# Esquema_el_tric.net
KiCad netlist of a schematic drawn in EAGLE
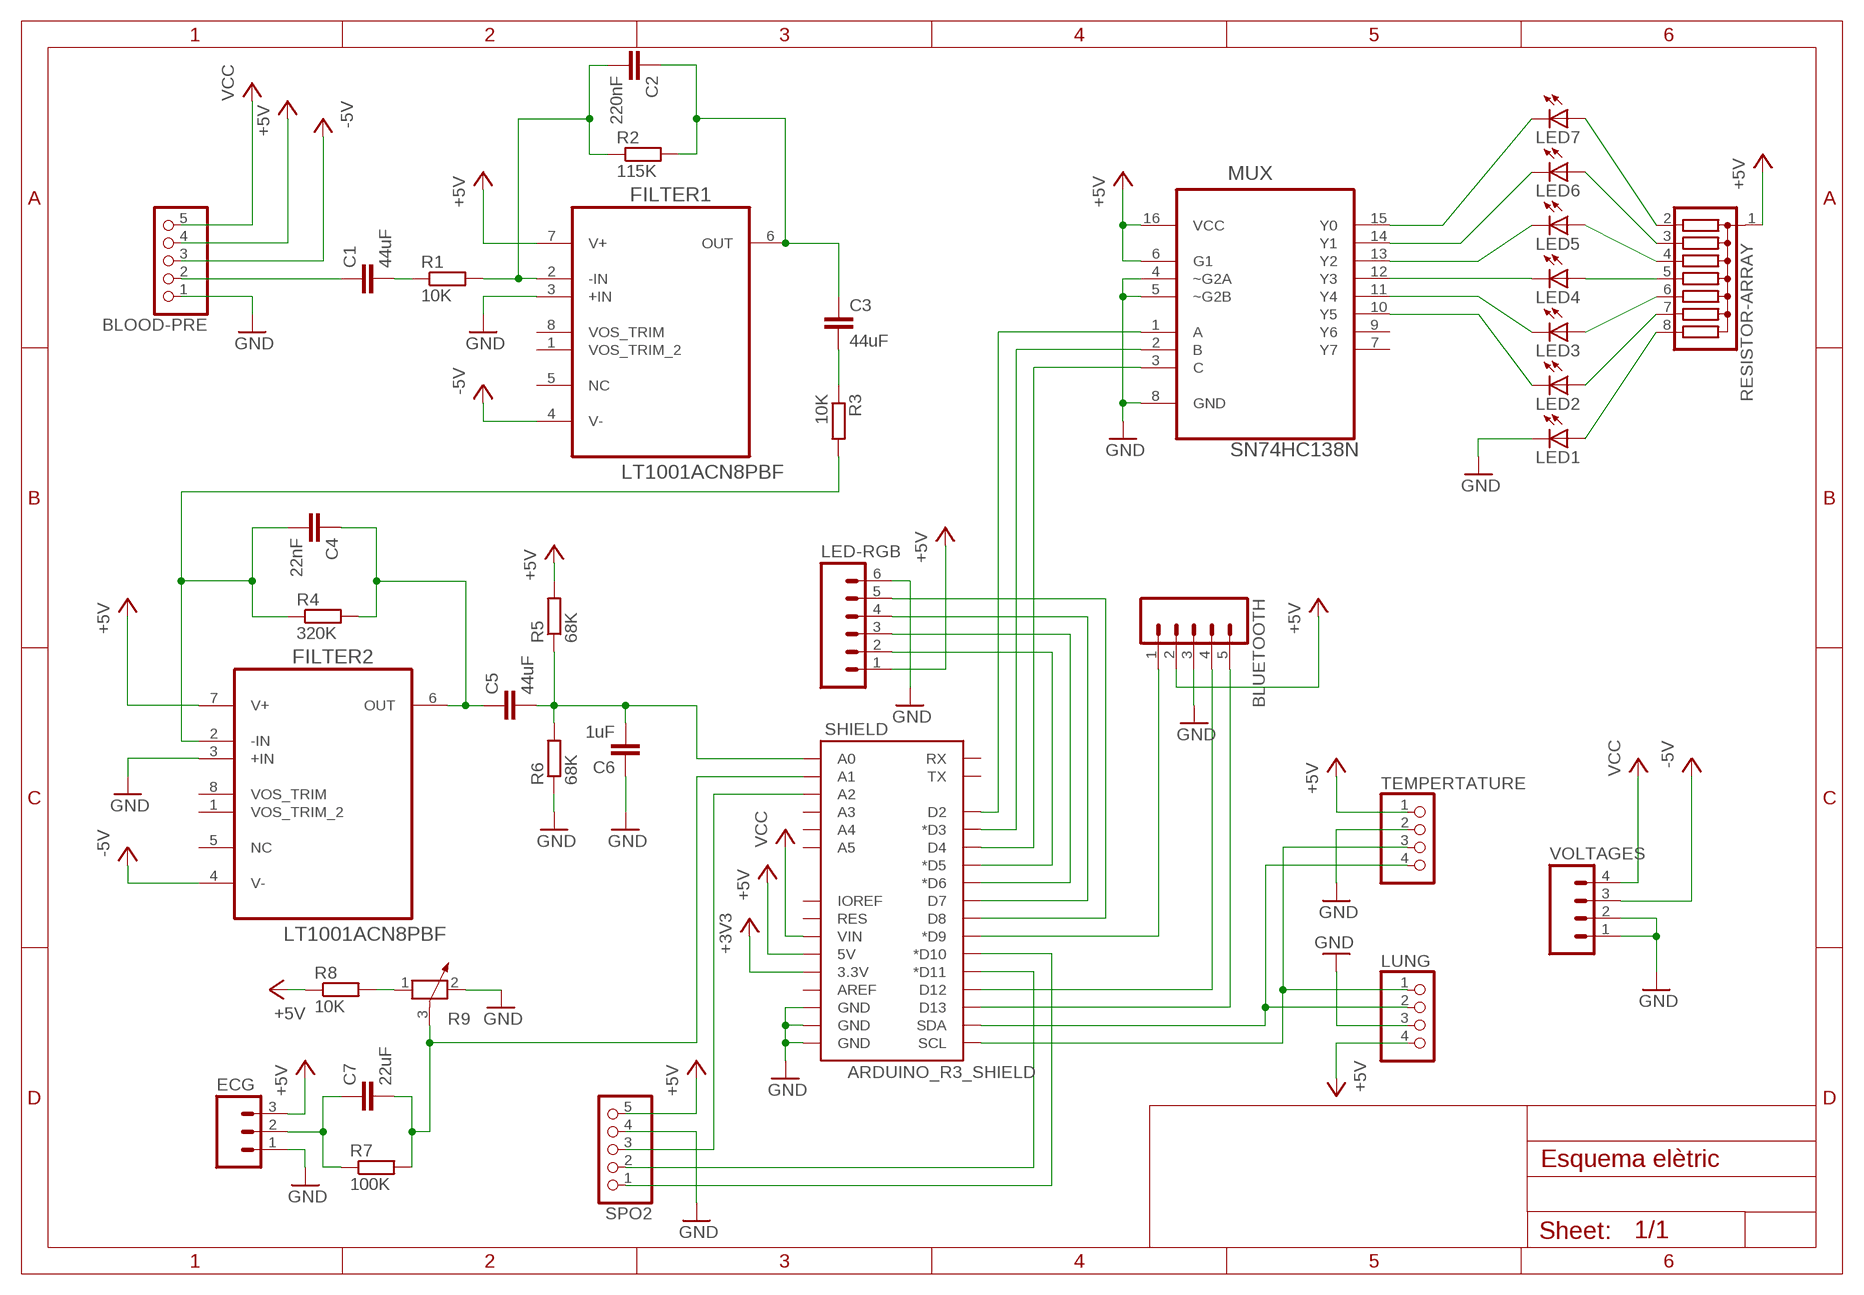
[diagram p0: schematic, sheet 1]

(export (version "E")
  (design (tool "Eeschema 10.0.6"))
  (components
    (comp (ref "BLOOD-PRE")
      (value "PINHD-1X5")
      (footprint "eagle-import:1X05")
      (libsource (lib "eagle-import") (part "PINHD-1X5"))
    )
    (comp (ref "BLUETOOTH")
      (value "M05PTH")
      (footprint "eagle-import:1X05")
      (libsource (lib "eagle-import") (part "M05PTH"))
    )
    (comp (ref "C1")
      (value "44uF")
      (footprint "eagle-import:C050-050X075")
      (libsource (lib "eagle-import") (part "C-EU050-050X075"))
    )
    (comp (ref "C2")
      (value "220nF")
      (footprint "eagle-import:C050-024X044")
      (libsource (lib "eagle-import") (part "C-EU050-024X044"))
    )
    (comp (ref "C3")
      (value "44uF")
      (footprint "eagle-import:C050-050X075")
      (libsource (lib "eagle-import") (part "C-EU050-050X075"))
    )
    (comp (ref "C4")
      (value "22nF")
      (footprint "eagle-import:C050-024X044")
      (libsource (lib "eagle-import") (part "C-EU050-024X044"))
    )
    (comp (ref "C5")
      (value "44uF")
      (footprint "eagle-import:C050-050X075")
      (libsource (lib "eagle-import") (part "C-EU050-050X075"))
    )
    (comp (ref "C6")
      (value "1uF")
      (footprint "eagle-import:C050-050X075")
      (libsource (lib "eagle-import") (part "C-EU050-050X075"))
    )
    (comp (ref "C7")
      (value "22uF")
      (footprint "eagle-import:C050-050X075")
      (libsource (lib "eagle-import") (part "C-EU050-050X075"))
    )
    (comp (ref "ECG")
      (value "M03PTH")
      (footprint "eagle-import:1X03")
      (libsource (lib "eagle-import") (part "M03PTH"))
    )
    (comp (ref "FILTER1")
      (value "LT1001ACN8PBF")
      (footprint "eagle-import:DIP254P762X393-8")
      (fields (field (name "MPN") "LT1001ACN8#PBF"))
      (libsource (lib "eagle-import") (part "LT1001ACN8PBF"))
    )
    (comp (ref "FILTER2")
      (value "LT1001ACN8PBF")
      (footprint "eagle-import:DIP254P762X393-8")
      (fields (field (name "MPN") "LT1001ACN8#PBF"))
      (libsource (lib "eagle-import") (part "LT1001ACN8PBF"))
    )
    (comp (ref "LED-RGB")
      (value "M06SILK_FEMALE_PTH")
      (footprint "eagle-import:1X06")
      (libsource (lib "eagle-import") (part "M06SILK_FEMALE_PTH"))
    )
    (comp (ref "LED1")
      (value "LED5MM")
      (footprint "eagle-import:LED5MM")
      (libsource (lib "eagle-import") (part "LED5MM"))
    )
    (comp (ref "LED2")
      (value "LED5MM")
      (footprint "eagle-import:LED5MM")
      (libsource (lib "eagle-import") (part "LED5MM"))
    )
    (comp (ref "LED3")
      (value "LED5MM")
      (footprint "eagle-import:LED5MM")
      (libsource (lib "eagle-import") (part "LED5MM"))
    )
    (comp (ref "LED4")
      (value "LED5MM")
      (footprint "eagle-import:LED5MM")
      (libsource (lib "eagle-import") (part "LED5MM"))
    )
    (comp (ref "LED5")
      (value "LED5MM")
      (footprint "eagle-import:LED5MM")
      (libsource (lib "eagle-import") (part "LED5MM"))
    )
    (comp (ref "LED6")
      (value "LED5MM")
      (footprint "eagle-import:LED5MM")
      (libsource (lib "eagle-import") (part "LED5MM"))
    )
    (comp (ref "LED7")
      (value "LED5MM")
      (footprint "eagle-import:LED5MM")
      (libsource (lib "eagle-import") (part "LED5MM"))
    )
    (comp (ref "LUNG")
      (value "PINHD-1X4")
      (footprint "eagle-import:1X04")
      (libsource (lib "eagle-import") (part "PINHD-1X4"))
    )
    (comp (ref "MUX")
      (value "SN74HC138N")
      (footprint "eagle-import:DIP254P762X508-16")
      (libsource (lib "eagle-import") (part "SN74HC138N"))
    )
    (comp (ref "R1")
      (value "10K")
      (footprint "eagle-import:0204_7")
      (libsource (lib "eagle-import") (part "R0204/7"))
    )
    (comp (ref "R2")
      (value "115K")
      (footprint "eagle-import:0204_7")
      (libsource (lib "eagle-import") (part "R0204/7"))
    )
    (comp (ref "R3")
      (value "10K")
      (footprint "eagle-import:0204_7")
      (libsource (lib "eagle-import") (part "R0204/7"))
    )
    (comp (ref "R4")
      (value "320K")
      (footprint "eagle-import:0204_7")
      (libsource (lib "eagle-import") (part "R0204/7"))
    )
    (comp (ref "R5")
      (value "68K")
      (footprint "eagle-import:0204_7")
      (libsource (lib "eagle-import") (part "R0204/7"))
    )
    (comp (ref "R6")
      (value "68K")
      (footprint "eagle-import:0204_7")
      (libsource (lib "eagle-import") (part "R0204/7"))
    )
    (comp (ref "R7")
      (value "100K")
      (footprint "eagle-import:0204_7")
      (libsource (lib "eagle-import") (part "R0204/7"))
    )
    (comp (ref "R8")
      (value "10K")
      (footprint "eagle-import:0204_7")
      (libsource (lib "eagle-import") (part "R0204/7"))
    )
    (comp (ref "R9")
      (value "POTENTIOMETER_PT-10")
      (footprint "eagle-import:PT-10")
      (libsource (lib "eagle-import") (part "POTENTIOMETER_PT-10"))
    )
    (comp (ref "RESISTOR-ARRAY")
      (value "G07R")
      (footprint "eagle-import:SIL8")
      (libsource (lib "eagle-import") (part "G07R"))
    )
    (comp (ref "SHIELD")
      (value "ARDUINO_R3_SHIELD")
      (footprint "eagle-import:UNO_R3_SHIELD")
      (libsource (lib "eagle-import") (part "ARDUINO_R3_SHIELD"))
    )
    (comp (ref "SPO2")
      (value "PINHD-1X5")
      (footprint "eagle-import:1X05")
      (libsource (lib "eagle-import") (part "PINHD-1X5"))
    )
    (comp (ref "TEMPERTATURE")
      (value "PINHD-1X4")
      (footprint "eagle-import:1X04")
      (libsource (lib "eagle-import") (part "PINHD-1X4"))
    )
    (comp (ref "VOLTAGES")
      (value "M04JST")
      (footprint "eagle-import:1X04-1.5MM_JST")
      (libsource (lib "eagle-import") (part "M04JST"))
    )
  )
  (nets
    (net (code "1") (name "+3V3") (class "Default")
      (node (ref "SHIELD") (pin "3.3V") (pinfunction "3.3V_3.3V") (pintype "bidirectional"))
    )
    (net (code "2") (name "+5V") (class "Default")
      (node (ref "BLOOD-PRE") (pin "4") (pinfunction "4_4") (pintype "passive"))
      (node (ref "BLUETOOTH") (pin "2") (pinfunction "2_2") (pintype "passive"))
      (node (ref "ECG") (pin "3") (pinfunction "3_3") (pintype "passive"))
      (node (ref "FILTER1") (pin "7") (pinfunction "V+_7") (pintype "power_in"))
      (node (ref "FILTER2") (pin "7") (pinfunction "V+_7") (pintype "power_in"))
      (node (ref "LED-RGB") (pin "1") (pinfunction "1_1") (pintype "passive"))
      (node (ref "LUNG") (pin "4") (pinfunction "4_4") (pintype "passive"))
      (node (ref "MUX") (pin "16") (pinfunction "VCC_16") (pintype "power_in"))
      (node (ref "MUX") (pin "6") (pinfunction "G1_6") (pintype "input"))
      (node (ref "R5") (pin "2") (pinfunction "2_2") (pintype "passive"))
      (node (ref "R8") (pin "1") (pinfunction "1_1") (pintype "passive"))
      (node (ref "RESISTOR-ARRAY") (pin "1") (pinfunction "1_1") (pintype "passive"))
      (node (ref "SHIELD") (pin "5V") (pinfunction "5V_5V") (pintype "bidirectional"))
      (node (ref "SPO2") (pin "5") (pinfunction "5_5") (pintype "passive"))
      (node (ref "TEMPERTATURE") (pin "1") (pinfunction "1_1") (pintype "passive"))
    )
    (net (code "3") (name "-5V") (class "Default")
      (node (ref "BLOOD-PRE") (pin "3") (pinfunction "3_3") (pintype "passive"))
      (node (ref "FILTER1") (pin "4") (pinfunction "V-_4") (pintype "power_in"))
      (node (ref "FILTER2") (pin "4") (pinfunction "V-_4") (pintype "power_in"))
      (node (ref "VOLTAGES") (pin "3") (pinfunction "3_3") (pintype "passive"))
    )
    (net (code "4") (name "GND") (class "Default")
      (node (ref "BLOOD-PRE") (pin "1") (pinfunction "1_1") (pintype "passive"))
      (node (ref "BLUETOOTH") (pin "3") (pinfunction "3_3") (pintype "passive"))
      (node (ref "C6") (pin "1") (pinfunction "1_1") (pintype "passive"))
      (node (ref "ECG") (pin "1") (pinfunction "1_1") (pintype "passive"))
      (node (ref "FILTER1") (pin "3") (pinfunction "+IN_3") (pintype "input"))
      (node (ref "FILTER2") (pin "3") (pinfunction "+IN_3") (pintype "input"))
      (node (ref "LED-RGB") (pin "6") (pinfunction "6_6") (pintype "passive"))
      (node (ref "LED1") (pin "K") (pinfunction "C_K") (pintype "passive"))
      (node (ref "LUNG") (pin "3") (pinfunction "3_3") (pintype "passive"))
      (node (ref "MUX") (pin "4") (pinfunction "~{G2A}_4") (pintype "input"))
      (node (ref "MUX") (pin "5") (pinfunction "~{G2B}_5") (pintype "input"))
      (node (ref "MUX") (pin "8") (pinfunction "GND_8") (pintype "passive"))
      (node (ref "R6") (pin "1") (pinfunction "1_1") (pintype "passive"))
      (node (ref "R9") (pin "2") (pinfunction "2_2") (pintype "passive"))
      (node (ref "SHIELD") (pin "GND@0") (pinfunction "GND_GND@0") (pintype "bidirectional"))
      (node (ref "SHIELD") (pin "GND@1") (pinfunction "GND_GND@1") (pintype "bidirectional"))
      (node (ref "SHIELD") (pin "GND@2") (pinfunction "GND_GND@2") (pintype "bidirectional"))
      (node (ref "SPO2") (pin "4") (pinfunction "4_4") (pintype "passive"))
      (node (ref "TEMPERTATURE") (pin "2") (pinfunction "2_2") (pintype "passive"))
      (node (ref "VOLTAGES") (pin "1") (pinfunction "1_1") (pintype "passive"))
      (node (ref "VOLTAGES") (pin "2") (pinfunction "2_2") (pintype "passive"))
    )
    (net (code "5") (name "Net-(BLOOD-PRE-Pad2)") (class "Default")
      (node (ref "BLOOD-PRE") (pin "2") (pinfunction "2_2") (pintype "passive"))
      (node (ref "C1") (pin "1") (pinfunction "1_1") (pintype "passive"))
    )
    (net (code "6") (name "Net-(BLUETOOTH-Pad4)") (class "Default")
      (node (ref "BLUETOOTH") (pin "4") (pinfunction "4_4") (pintype "passive"))
      (node (ref "SHIELD") (pin "D12") (pinfunction "D12_D12") (pintype "bidirectional"))
    )
    (net (code "7") (name "Net-(BLUETOOTH-Pad5)") (class "Default")
      (node (ref "BLUETOOTH") (pin "5") (pinfunction "5_5") (pintype "passive"))
      (node (ref "SHIELD") (pin "D13") (pinfunction "D13_D13") (pintype "bidirectional"))
    )
    (net (code "8") (name "Net-(C1-Pad2)") (class "Default")
      (node (ref "C1") (pin "2") (pinfunction "2_2") (pintype "passive"))
      (node (ref "R1") (pin "1") (pinfunction "1_1") (pintype "passive"))
    )
    (net (code "9") (name "Net-(C3-Pad2)") (class "Default")
      (node (ref "C3") (pin "2") (pinfunction "2_2") (pintype "passive"))
      (node (ref "R3") (pin "1") (pinfunction "1_1") (pintype "passive"))
    )
    (net (code "10") (name "Net-(C5-Pad2)") (class "Default")
      (node (ref "C5") (pin "2") (pinfunction "2_2") (pintype "passive"))
      (node (ref "C6") (pin "2") (pinfunction "2_2") (pintype "passive"))
      (node (ref "R5") (pin "1") (pinfunction "1_1") (pintype "passive"))
      (node (ref "R6") (pin "2") (pinfunction "2_2") (pintype "passive"))
      (node (ref "SHIELD") (pin "A0") (pinfunction "A0_A0") (pintype "bidirectional"))
    )
    (net (code "11") (name "Net-(C7-Pad1)") (class "Default")
      (node (ref "C7") (pin "1") (pinfunction "1_1") (pintype "passive"))
      (node (ref "ECG") (pin "2") (pinfunction "2_2") (pintype "passive"))
      (node (ref "R7") (pin "1") (pinfunction "1_1") (pintype "passive"))
    )
    (net (code "12") (name "Net-(C7-Pad2)") (class "Default")
      (node (ref "C7") (pin "2") (pinfunction "2_2") (pintype "passive"))
      (node (ref "R7") (pin "2") (pinfunction "2_2") (pintype "passive"))
      (node (ref "R9") (pin "3") (pinfunction "3_3") (pintype "passive"))
      (node (ref "SHIELD") (pin "A1") (pinfunction "A1_A1") (pintype "bidirectional"))
    )
    (net (code "13") (name "Net-(FILTER1--IN)") (class "Default")
      (node (ref "C2") (pin "2") (pinfunction "2_2") (pintype "passive"))
      (node (ref "FILTER1") (pin "2") (pinfunction "-IN_2") (pintype "input"))
      (node (ref "R1") (pin "2") (pinfunction "2_2") (pintype "passive"))
      (node (ref "R2") (pin "1") (pinfunction "1_1") (pintype "passive"))
    )
    (net (code "14") (name "Net-(FILTER1-OUT)") (class "Default")
      (node (ref "C2") (pin "1") (pinfunction "1_1") (pintype "passive"))
      (node (ref "C3") (pin "1") (pinfunction "1_1") (pintype "passive"))
      (node (ref "FILTER1") (pin "6") (pinfunction "OUT_6") (pintype "output"))
      (node (ref "R2") (pin "2") (pinfunction "2_2") (pintype "passive"))
    )
    (net (code "15") (name "Net-(FILTER2--IN)") (class "Default")
      (node (ref "C4") (pin "2") (pinfunction "2_2") (pintype "passive"))
      (node (ref "FILTER2") (pin "2") (pinfunction "-IN_2") (pintype "input"))
      (node (ref "R3") (pin "2") (pinfunction "2_2") (pintype "passive"))
      (node (ref "R4") (pin "1") (pinfunction "1_1") (pintype "passive"))
    )
    (net (code "16") (name "Net-(FILTER2-OUT)") (class "Default")
      (node (ref "C4") (pin "1") (pinfunction "1_1") (pintype "passive"))
      (node (ref "C5") (pin "1") (pinfunction "1_1") (pintype "passive"))
      (node (ref "FILTER2") (pin "6") (pinfunction "OUT_6") (pintype "output"))
      (node (ref "R4") (pin "2") (pinfunction "2_2") (pintype "passive"))
    )
    (net (code "17") (name "Net-(LED-RGB-Pad4)") (class "Default")
      (node (ref "LED-RGB") (pin "4") (pinfunction "4_4") (pintype "passive"))
      (node (ref "SHIELD") (pin "D7") (pinfunction "D7_D7") (pintype "bidirectional"))
    )
    (net (code "18") (name "Net-(LED-RGB-Pad5)") (class "Default")
      (node (ref "LED-RGB") (pin "5") (pinfunction "5_5") (pintype "passive"))
      (node (ref "SHIELD") (pin "D8") (pinfunction "D8_D8") (pintype "bidirectional"))
    )
    (net (code "19") (name "Net-(LED1-PadA)") (class "Default")
      (node (ref "LED1") (pin "A") (pinfunction "A_A") (pintype "passive"))
      (node (ref "RESISTOR-ARRAY") (pin "8") (pinfunction "8_8") (pintype "passive"))
    )
    (net (code "20") (name "Net-(LED2-C)") (class "Default")
      (node (ref "LED2") (pin "K") (pinfunction "C_K") (pintype "passive"))
      (node (ref "MUX") (pin "10") (pinfunction "Y5_10") (pintype "output"))
    )
    (net (code "21") (name "Net-(LED2-PadA)") (class "Default")
      (node (ref "LED2") (pin "A") (pinfunction "A_A") (pintype "passive"))
      (node (ref "RESISTOR-ARRAY") (pin "7") (pinfunction "7_7") (pintype "passive"))
    )
    (net (code "22") (name "Net-(LED3-C)") (class "Default")
      (node (ref "LED3") (pin "K") (pinfunction "C_K") (pintype "passive"))
      (node (ref "MUX") (pin "11") (pinfunction "Y4_11") (pintype "output"))
    )
    (net (code "23") (name "Net-(LED3-PadA)") (class "Default")
      (node (ref "LED3") (pin "A") (pinfunction "A_A") (pintype "passive"))
      (node (ref "RESISTOR-ARRAY") (pin "6") (pinfunction "6_6") (pintype "passive"))
    )
    (net (code "24") (name "Net-(LED4-C)") (class "Default")
      (node (ref "LED4") (pin "K") (pinfunction "C_K") (pintype "passive"))
      (node (ref "MUX") (pin "12") (pinfunction "Y3_12") (pintype "output"))
    )
    (net (code "25") (name "Net-(LED4-PadA)") (class "Default")
      (node (ref "LED4") (pin "A") (pinfunction "A_A") (pintype "passive"))
      (node (ref "RESISTOR-ARRAY") (pin "5") (pinfunction "5_5") (pintype "passive"))
    )
    (net (code "26") (name "Net-(LED5-C)") (class "Default")
      (node (ref "LED5") (pin "K") (pinfunction "C_K") (pintype "passive"))
      (node (ref "MUX") (pin "13") (pinfunction "Y2_13") (pintype "output"))
    )
    (net (code "27") (name "Net-(LED5-PadA)") (class "Default")
      (node (ref "LED5") (pin "A") (pinfunction "A_A") (pintype "passive"))
      (node (ref "RESISTOR-ARRAY") (pin "4") (pinfunction "4_4") (pintype "passive"))
    )
    (net (code "28") (name "Net-(LED6-C)") (class "Default")
      (node (ref "LED6") (pin "K") (pinfunction "C_K") (pintype "passive"))
      (node (ref "MUX") (pin "14") (pinfunction "Y1_14") (pintype "output"))
    )
    (net (code "29") (name "Net-(LED6-PadA)") (class "Default")
      (node (ref "LED6") (pin "A") (pinfunction "A_A") (pintype "passive"))
      (node (ref "RESISTOR-ARRAY") (pin "3") (pinfunction "3_3") (pintype "passive"))
    )
    (net (code "30") (name "Net-(LED7-C)") (class "Default")
      (node (ref "LED7") (pin "K") (pinfunction "C_K") (pintype "passive"))
      (node (ref "MUX") (pin "15") (pinfunction "Y0_15") (pintype "output"))
    )
    (net (code "31") (name "Net-(LED7-PadA)") (class "Default")
      (node (ref "LED7") (pin "A") (pinfunction "A_A") (pintype "passive"))
      (node (ref "RESISTOR-ARRAY") (pin "2") (pinfunction "2_2") (pintype "passive"))
    )
    (net (code "32") (name "Net-(LUNG-Pad1)") (class "Default")
      (node (ref "LUNG") (pin "1") (pinfunction "1_1") (pintype "passive"))
      (node (ref "SHIELD") (pin "SCL") (pinfunction "SCL_SCL") (pintype "bidirectional"))
      (node (ref "TEMPERTATURE") (pin "3") (pinfunction "3_3") (pintype "passive"))
    )
    (net (code "33") (name "Net-(LUNG-Pad2)") (class "Default")
      (node (ref "LUNG") (pin "2") (pinfunction "2_2") (pintype "passive"))
      (node (ref "SHIELD") (pin "SDA") (pinfunction "SDA_SDA") (pintype "bidirectional"))
      (node (ref "TEMPERTATURE") (pin "4") (pinfunction "4_4") (pintype "passive"))
    )
    (net (code "34") (name "Net-(MUX-A)") (class "Default")
      (node (ref "MUX") (pin "1") (pinfunction "A_1") (pintype "input"))
      (node (ref "SHIELD") (pin "D2") (pinfunction "D2_D2") (pintype "bidirectional"))
    )
    (net (code "35") (name "Net-(MUX-B)") (class "Default")
      (node (ref "MUX") (pin "2") (pinfunction "B_2") (pintype "input"))
      (node (ref "SHIELD") (pin "D3") (pinfunction "*D3_D3") (pintype "bidirectional"))
    )
    (net (code "36") (name "Net-(MUX-C)") (class "Default")
      (node (ref "MUX") (pin "3") (pinfunction "C_3") (pintype "input"))
      (node (ref "SHIELD") (pin "D4") (pinfunction "D4_D4") (pintype "bidirectional"))
    )
    (net (code "37") (name "Net-(R8-Pad2)") (class "Default")
      (node (ref "R8") (pin "2") (pinfunction "2_2") (pintype "passive"))
      (node (ref "R9") (pin "1") (pinfunction "1_1") (pintype "passive"))
    )
    (net (code "38") (name "Net-(SHIELD-*D5)") (class "Default")
      (node (ref "LED-RGB") (pin "2") (pinfunction "2_2") (pintype "passive"))
      (node (ref "SHIELD") (pin "D5") (pinfunction "*D5_D5") (pintype "bidirectional"))
    )
    (net (code "39") (name "Net-(SHIELD-*D6)") (class "Default")
      (node (ref "LED-RGB") (pin "3") (pinfunction "3_3") (pintype "passive"))
      (node (ref "SHIELD") (pin "D6") (pinfunction "*D6_D6") (pintype "bidirectional"))
    )
    (net (code "40") (name "Net-(SHIELD-*D9)") (class "Default")
      (node (ref "BLUETOOTH") (pin "1") (pinfunction "1_1") (pintype "passive"))
      (node (ref "SHIELD") (pin "D9") (pinfunction "*D9_D9") (pintype "bidirectional"))
    )
    (net (code "41") (name "Net-(SHIELD-*D10)") (class "Default")
      (node (ref "SHIELD") (pin "D10") (pinfunction "*D10_D10") (pintype "bidirectional"))
      (node (ref "SPO2") (pin "1") (pinfunction "1_1") (pintype "passive"))
    )
    (net (code "42") (name "Net-(SHIELD-*D11)") (class "Default")
      (node (ref "SHIELD") (pin "D11") (pinfunction "*D11_D11") (pintype "bidirectional"))
      (node (ref "SPO2") (pin "2") (pinfunction "2_2") (pintype "passive"))
    )
    (net (code "43") (name "Net-(SHIELD-PadA2)") (class "Default")
      (node (ref "SHIELD") (pin "A2") (pinfunction "A2_A2") (pintype "bidirectional"))
      (node (ref "SPO2") (pin "3") (pinfunction "3_3") (pintype "passive"))
    )
    (net (code "44") (name "VCC") (class "Default")
      (node (ref "BLOOD-PRE") (pin "5") (pinfunction "5_5") (pintype "passive"))
      (node (ref "SHIELD") (pin "VIN") (pinfunction "VIN_VIN") (pintype "bidirectional"))
      (node (ref "VOLTAGES") (pin "4") (pinfunction "4_4") (pintype "passive"))
    )
    (net (code "45") (name "unconnected-(FILTER1-NC-Pad5)") (class "Default")
      (node (ref "FILTER1") (pin "5") (pinfunction "NC_5") (pintype "no_connect"))
    )
    (net (code "46") (name "unconnected-(FILTER1-VOS_TRIM-Pad8)") (class "Default")
      (node (ref "FILTER1") (pin "8") (pinfunction "VOS_TRIM_8") (pintype "passive"))
    )
    (net (code "47") (name "unconnected-(FILTER1-VOS_TRIM_2-Pad1)") (class "Default")
      (node (ref "FILTER1") (pin "1") (pinfunction "VOS_TRIM_2_1") (pintype "passive"))
    )
    (net (code "48") (name "unconnected-(FILTER2-NC-Pad5)") (class "Default")
      (node (ref "FILTER2") (pin "5") (pinfunction "NC_5") (pintype "no_connect"))
    )
    (net (code "49") (name "unconnected-(FILTER2-VOS_TRIM-Pad8)") (class "Default")
      (node (ref "FILTER2") (pin "8") (pinfunction "VOS_TRIM_8") (pintype "passive"))
    )
    (net (code "50") (name "unconnected-(FILTER2-VOS_TRIM_2-Pad1)") (class "Default")
      (node (ref "FILTER2") (pin "1") (pinfunction "VOS_TRIM_2_1") (pintype "passive"))
    )
    (net (code "51") (name "unconnected-(MUX-Y6-Pad9)") (class "Default")
      (node (ref "MUX") (pin "9") (pinfunction "Y6_9") (pintype "output"))
    )
    (net (code "52") (name "unconnected-(MUX-Y7-Pad7)") (class "Default")
      (node (ref "MUX") (pin "7") (pinfunction "Y7_7") (pintype "output"))
    )
    (net (code "53") (name "unconnected-(SHIELD-PadA3)") (class "Default")
      (node (ref "SHIELD") (pin "A3") (pinfunction "A3_A3") (pintype "bidirectional"))
    )
    (net (code "54") (name "unconnected-(SHIELD-PadA4)") (class "Default")
      (node (ref "SHIELD") (pin "A4") (pinfunction "A4_A4") (pintype "bidirectional"))
    )
    (net (code "55") (name "unconnected-(SHIELD-PadA5)") (class "Default")
      (node (ref "SHIELD") (pin "A5") (pinfunction "A5_A5") (pintype "bidirectional"))
    )
    (net (code "56") (name "unconnected-(SHIELD-PadAREF)") (class "Default")
      (node (ref "SHIELD") (pin "AREF") (pinfunction "AREF_AREF") (pintype "bidirectional"))
    )
    (net (code "57") (name "unconnected-(SHIELD-PadIOREF)") (class "Default")
      (node (ref "SHIELD") (pin "IOREF") (pinfunction "IOREF_IOREF") (pintype "bidirectional"))
    )
    (net (code "58") (name "unconnected-(SHIELD-PadRES)") (class "Default")
      (node (ref "SHIELD") (pin "RES") (pinfunction "RES_RES") (pintype "bidirectional"))
    )
    (net (code "59") (name "unconnected-(SHIELD-PadRX)") (class "Default")
      (node (ref "SHIELD") (pin "RX") (pinfunction "RX_RX") (pintype "bidirectional"))
    )
    (net (code "60") (name "unconnected-(SHIELD-PadTX)") (class "Default")
      (node (ref "SHIELD") (pin "TX") (pinfunction "TX_TX") (pintype "bidirectional"))
    )
  )
)
